# controller_SHIM.net
KiCad netlist of a schematic drawn in EAGLE
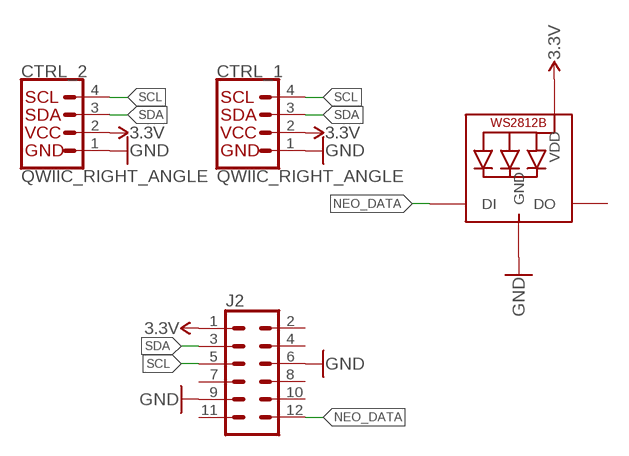
[diagram p0: schematic, sheet 1]

(export (version "E")
  (design (tool "Eeschema 10.0.6"))
  (components
    (comp (ref "CTRL_1")
      (value "QWIIC_RIGHT_ANGLE")
      (footprint "eagle-import:JST04_1MM_RA")
      (libsource (lib "eagle-import") (part "QWIIC_CONNECTORJS-1MM"))
    )
    (comp (ref "CTRL_2")
      (value "QWIIC_RIGHT_ANGLE")
      (footprint "eagle-import:JST04_1MM_RA")
      (libsource (lib "eagle-import") (part "QWIIC_CONNECTORJS-1MM"))
    )
    (comp (ref "J2")
      (value "CONN_06X2SMD_FEMALE")
      (footprint "eagle-import:2X6_SMD")
      (libsource (lib "eagle-import") (part "CONN_06X2SMD_FEMALE"))
    )
    (comp (ref "STATUS_LED")
      (value "WS2812B3535")
      (footprint "eagle-import:LED3535")
      (libsource (lib "eagle-import") (part "WS2812B3535"))
    )
  )
  (nets
    (net (code "1") (name "3.3V") (class "Default")
      (node (ref "CTRL_1") (pin "2") (pinfunction "2_2") (pintype "power_in"))
      (node (ref "CTRL_2") (pin "2") (pinfunction "2_2") (pintype "power_in"))
      (node (ref "J2") (pin "1") (pinfunction "1_1") (pintype "passive"))
      (node (ref "STATUS_LED") (pin "2") (pinfunction "VDD_2") (pintype "power_in"))
    )
    (net (code "2") (name "GND") (class "Default")
      (node (ref "CTRL_1") (pin "1") (pinfunction "1_1") (pintype "power_in"))
      (node (ref "CTRL_2") (pin "1") (pinfunction "1_1") (pintype "power_in"))
      (node (ref "J2") (pin "6") (pinfunction "6_6") (pintype "passive"))
      (node (ref "J2") (pin "9") (pinfunction "9_9") (pintype "passive"))
      (node (ref "STATUS_LED") (pin "4") (pinfunction "GND_4") (pintype "power_in"))
    )
    (net (code "3") (name "NEO_DATA") (class "Default")
      (node (ref "J2") (pin "12") (pinfunction "12_12") (pintype "passive"))
      (node (ref "STATUS_LED") (pin "1") (pinfunction "DI_1") (pintype "input"))
    )
    (net (code "4") (name "SCL") (class "Default")
      (node (ref "CTRL_1") (pin "4") (pinfunction "4_4") (pintype "passive"))
      (node (ref "CTRL_2") (pin "4") (pinfunction "4_4") (pintype "passive"))
      (node (ref "J2") (pin "5") (pinfunction "5_5") (pintype "passive"))
    )
    (net (code "5") (name "SDA") (class "Default")
      (node (ref "CTRL_1") (pin "3") (pinfunction "3_3") (pintype "passive"))
      (node (ref "CTRL_2") (pin "3") (pinfunction "3_3") (pintype "passive"))
      (node (ref "J2") (pin "3") (pinfunction "3_3") (pintype "passive"))
    )
    (net (code "6") (name "unconnected-(J2-Pad2)") (class "Default")
      (node (ref "J2") (pin "2") (pinfunction "2_2") (pintype "passive"))
    )
    (net (code "7") (name "unconnected-(J2-Pad4)") (class "Default")
      (node (ref "J2") (pin "4") (pinfunction "4_4") (pintype "passive"))
    )
    (net (code "8") (name "unconnected-(J2-Pad7)") (class "Default")
      (node (ref "J2") (pin "7") (pinfunction "7_7") (pintype "passive"))
    )
    (net (code "9") (name "unconnected-(J2-Pad8)") (class "Default")
      (node (ref "J2") (pin "8") (pinfunction "8_8") (pintype "passive"))
    )
    (net (code "10") (name "unconnected-(J2-Pad10)") (class "Default")
      (node (ref "J2") (pin "10") (pinfunction "10_10") (pintype "passive"))
    )
    (net (code "11") (name "unconnected-(J2-Pad11)") (class "Default")
      (node (ref "J2") (pin "11") (pinfunction "11_11") (pintype "passive"))
    )
    (net (code "12") (name "unconnected-(STATUS_LED-DO-Pad3)") (class "Default")
      (node (ref "STATUS_LED") (pin "3") (pinfunction "DO_3") (pintype "output"))
    )
  )
)
